# main.net
KiCad netlist of a schematic drawn in EAGLE
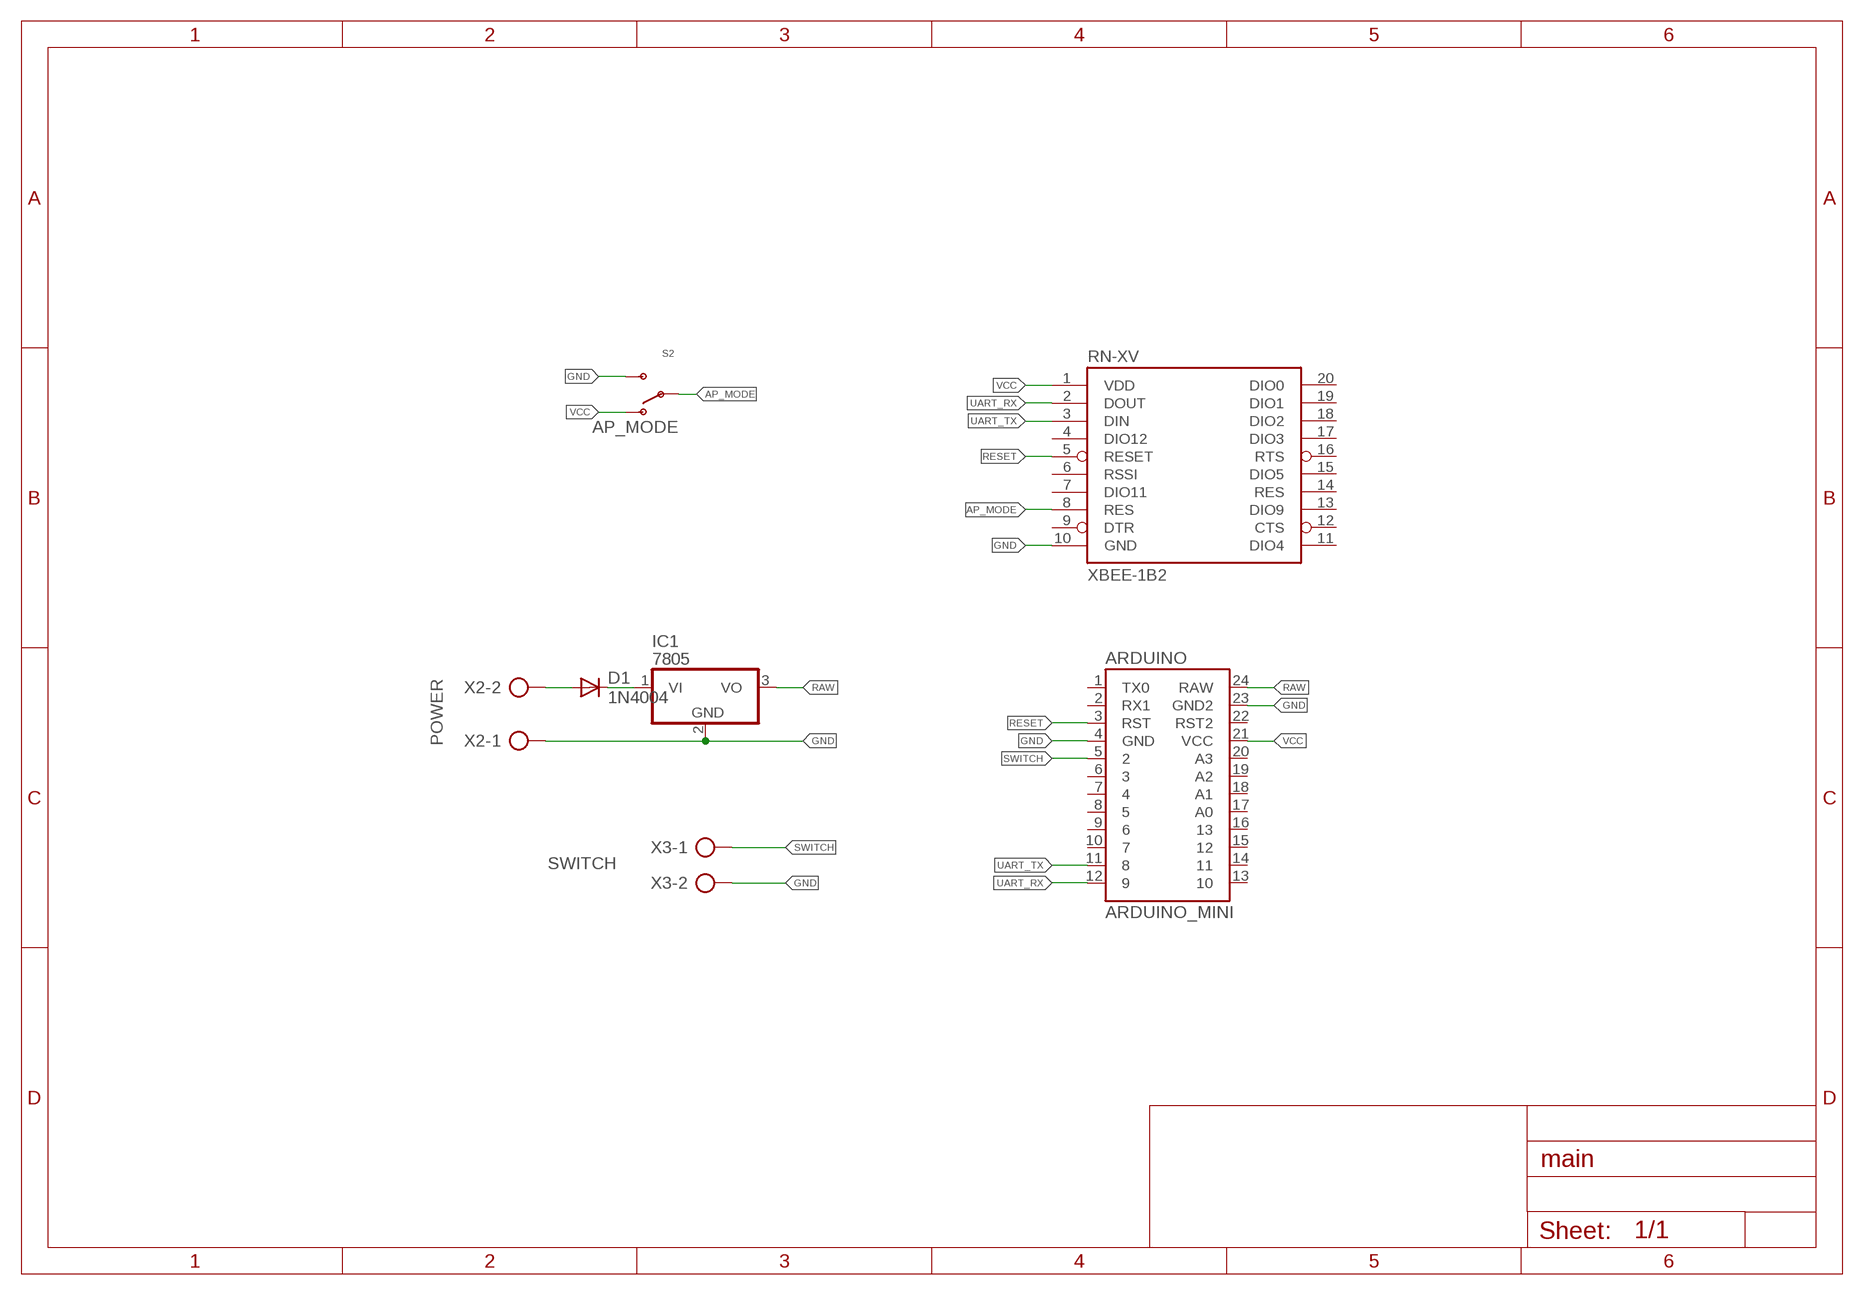
[diagram p0: schematic, sheet 1]

(export (version "E")
  (design (tool "Eeschema 10.0.6"))
  (components
    (comp (ref "ARDUINO")
      (value "ARDUINO_MINI")
      (footprint "eagle-import:ARDUINO_MINI")
      (libsource (lib "eagle-import") (part "ARDUINO_MINI"))
    )
    (comp (ref "D1")
      (value "1N4004")
      (footprint "eagle-import:DO41-10")
      (libsource (lib "eagle-import") (part "1N4004"))
    )
    (comp (ref "IC1")
      (value "7805")
      (footprint "eagle-import:TO220V")
      (libsource (lib "eagle-import") (part "78TV6"))
    )
    (comp (ref "RN-XV")
      (value "XBEE-1B2")
      (footprint "eagle-import:XBEE-SILK")
      (libsource (lib "eagle-import") (part "XBEE-1B2"))
    )
    (comp (ref "S2")
      (value "AP_MODE")
      (footprint "eagle-import:SWITCH-SPDT")
      (libsource (lib "eagle-import") (part "SWITCH-SPDTPTH"))
    )
    (comp (ref "X2")
      (value "POWER")
      (footprint "eagle-import:AK500_2")
      (libsource (lib "eagle-import") (part "AK500/2"))
    )
    (comp (ref "X3")
      (value "SWITCH")
      (footprint "eagle-import:AK500_2")
      (fields (field (name "OC_FARNELL") "unknown") (field (name "OC_NEWARK") "unknown"))
      (libsource (lib "eagle-import") (part "AK500/2"))
    )
  )
  (nets
    (net (code "1") (name "AP_MODE") (class "Default")
      (node (ref "RN-XV") (pin "8") (pinfunction "RES_8") (pintype "bidirectional"))
      (node (ref "S2") (pin "2") (pinfunction "P_2") (pintype "passive"))
    )
    (net (code "2") (name "GND") (class "Default")
      (node (ref "ARDUINO") (pin "23") (pinfunction "GND2_23") (pintype "bidirectional"))
      (node (ref "ARDUINO") (pin "4") (pinfunction "GND_4") (pintype "bidirectional"))
      (node (ref "IC1") (pin "2") (pinfunction "GND_2") (pintype "passive"))
      (node (ref "RN-XV") (pin "10") (pinfunction "GND_10") (pintype "power_in"))
      (node (ref "S2") (pin "3") (pinfunction "S_3") (pintype "passive"))
      (node (ref "X2") (pin "1") (pinfunction "KL_1") (pintype "passive"))
      (node (ref "X3") (pin "2") (pinfunction "KL_2") (pintype "passive"))
    )
    (net (code "3") (name "Net-(IC1-VI)") (class "Default")
      (node (ref "D1") (pin "C") (pinfunction "C_C") (pintype "passive"))
      (node (ref "IC1") (pin "1") (pinfunction "VI_1") (pintype "input"))
    )
    (net (code "4") (name "Net-(X2B-KL)") (class "Default")
      (node (ref "D1") (pin "A") (pinfunction "A_A") (pintype "passive"))
      (node (ref "X2") (pin "2") (pinfunction "KL_2") (pintype "passive"))
    )
    (net (code "5") (name "RAW") (class "Default")
      (node (ref "ARDUINO") (pin "24") (pinfunction "RAW_24") (pintype "bidirectional"))
      (node (ref "IC1") (pin "3") (pinfunction "VO_3") (pintype "passive"))
    )
    (net (code "6") (name "RESET") (class "Default")
      (node (ref "ARDUINO") (pin "3") (pinfunction "RST_3") (pintype "bidirectional"))
      (node (ref "RN-XV") (pin "5") (pinfunction "RESET_5") (pintype "input"))
    )
    (net (code "7") (name "SWITCH") (class "Default")
      (node (ref "ARDUINO") (pin "5") (pinfunction "2_5") (pintype "bidirectional"))
      (node (ref "X3") (pin "1") (pinfunction "KL_1") (pintype "passive"))
    )
    (net (code "8") (name "UART_RX") (class "Default")
      (node (ref "ARDUINO") (pin "12") (pinfunction "9_12") (pintype "bidirectional"))
      (node (ref "RN-XV") (pin "2") (pinfunction "DOUT_2") (pintype "output"))
    )
    (net (code "9") (name "UART_TX") (class "Default")
      (node (ref "ARDUINO") (pin "11") (pinfunction "8_11") (pintype "bidirectional"))
      (node (ref "RN-XV") (pin "3") (pinfunction "DIN_3") (pintype "input"))
    )
    (net (code "10") (name "VCC") (class "Default")
      (node (ref "ARDUINO") (pin "21") (pinfunction "VCC_21") (pintype "bidirectional"))
      (node (ref "RN-XV") (pin "1") (pinfunction "VDD_1") (pintype "power_in"))
      (node (ref "S2") (pin "1") (pinfunction "O_1") (pintype "passive"))
    )
    (net (code "11") (name "unconnected-(ARDUINO-3-Pad6)") (class "Default")
      (node (ref "ARDUINO") (pin "6") (pinfunction "3_6") (pintype "bidirectional"))
    )
    (net (code "12") (name "unconnected-(ARDUINO-4-Pad7)") (class "Default")
      (node (ref "ARDUINO") (pin "7") (pinfunction "4_7") (pintype "bidirectional"))
    )
    (net (code "13") (name "unconnected-(ARDUINO-5-Pad8)") (class "Default")
      (node (ref "ARDUINO") (pin "8") (pinfunction "5_8") (pintype "bidirectional"))
    )
    (net (code "14") (name "unconnected-(ARDUINO-6-Pad9)") (class "Default")
      (node (ref "ARDUINO") (pin "9") (pinfunction "6_9") (pintype "bidirectional"))
    )
    (net (code "15") (name "unconnected-(ARDUINO-7-Pad10)") (class "Default")
      (node (ref "ARDUINO") (pin "10") (pinfunction "7_10") (pintype "bidirectional"))
    )
    (net (code "16") (name "unconnected-(ARDUINO-10-Pad13)") (class "Default")
      (node (ref "ARDUINO") (pin "13") (pinfunction "10_13") (pintype "bidirectional"))
    )
    (net (code "17") (name "unconnected-(ARDUINO-11-Pad14)") (class "Default")
      (node (ref "ARDUINO") (pin "14") (pinfunction "11_14") (pintype "bidirectional"))
    )
    (net (code "18") (name "unconnected-(ARDUINO-12-Pad15)") (class "Default")
      (node (ref "ARDUINO") (pin "15") (pinfunction "12_15") (pintype "bidirectional"))
    )
    (net (code "19") (name "unconnected-(ARDUINO-13-Pad16)") (class "Default")
      (node (ref "ARDUINO") (pin "16") (pinfunction "13_16") (pintype "bidirectional"))
    )
    (net (code "20") (name "unconnected-(ARDUINO-A0-Pad17)") (class "Default")
      (node (ref "ARDUINO") (pin "17") (pinfunction "A0_17") (pintype "bidirectional"))
    )
    (net (code "21") (name "unconnected-(ARDUINO-A1-Pad18)") (class "Default")
      (node (ref "ARDUINO") (pin "18") (pinfunction "A1_18") (pintype "bidirectional"))
    )
    (net (code "22") (name "unconnected-(ARDUINO-A2-Pad19)") (class "Default")
      (node (ref "ARDUINO") (pin "19") (pinfunction "A2_19") (pintype "bidirectional"))
    )
    (net (code "23") (name "unconnected-(ARDUINO-A3-Pad20)") (class "Default")
      (node (ref "ARDUINO") (pin "20") (pinfunction "A3_20") (pintype "bidirectional"))
    )
    (net (code "24") (name "unconnected-(ARDUINO-RST2-Pad22)") (class "Default")
      (node (ref "ARDUINO") (pin "22") (pinfunction "RST2_22") (pintype "bidirectional"))
    )
    (net (code "25") (name "unconnected-(ARDUINO-RX1-Pad2)") (class "Default")
      (node (ref "ARDUINO") (pin "2") (pinfunction "RX1_2") (pintype "bidirectional"))
    )
    (net (code "26") (name "unconnected-(ARDUINO-TX0-Pad1)") (class "Default")
      (node (ref "ARDUINO") (pin "1") (pinfunction "TX0_1") (pintype "bidirectional"))
    )
    (net (code "27") (name "unconnected-(RN-XV-CTS-Pad12)") (class "Default")
      (node (ref "RN-XV") (pin "12") (pinfunction "CTS_12") (pintype "output"))
    )
    (net (code "28") (name "unconnected-(RN-XV-DIO0-Pad20)") (class "Default")
      (node (ref "RN-XV") (pin "20") (pinfunction "DIO0_20") (pintype "bidirectional"))
    )
    (net (code "29") (name "unconnected-(RN-XV-DIO1-Pad19)") (class "Default")
      (node (ref "RN-XV") (pin "19") (pinfunction "DIO1_19") (pintype "bidirectional"))
    )
    (net (code "30") (name "unconnected-(RN-XV-DIO2-Pad18)") (class "Default")
      (node (ref "RN-XV") (pin "18") (pinfunction "DIO2_18") (pintype "bidirectional"))
    )
    (net (code "31") (name "unconnected-(RN-XV-DIO3-Pad17)") (class "Default")
      (node (ref "RN-XV") (pin "17") (pinfunction "DIO3_17") (pintype "bidirectional"))
    )
    (net (code "32") (name "unconnected-(RN-XV-DIO4-Pad11)") (class "Default")
      (node (ref "RN-XV") (pin "11") (pinfunction "DIO4_11") (pintype "bidirectional"))
    )
    (net (code "33") (name "unconnected-(RN-XV-DIO5-Pad15)") (class "Default")
      (node (ref "RN-XV") (pin "15") (pinfunction "DIO5_15") (pintype "bidirectional"))
    )
    (net (code "34") (name "unconnected-(RN-XV-DIO9-Pad13)") (class "Default")
      (node (ref "RN-XV") (pin "13") (pinfunction "DIO9_13") (pintype "bidirectional"))
    )
    (net (code "35") (name "unconnected-(RN-XV-DIO11-Pad7)") (class "Default")
      (node (ref "RN-XV") (pin "7") (pinfunction "DIO11_7") (pintype "bidirectional"))
    )
    (net (code "36") (name "unconnected-(RN-XV-DIO12-Pad4)") (class "Default")
      (node (ref "RN-XV") (pin "4") (pinfunction "DIO12_4") (pintype "bidirectional"))
    )
    (net (code "37") (name "unconnected-(RN-XV-DTR-Pad9)") (class "Default")
      (node (ref "RN-XV") (pin "9") (pinfunction "DTR_9") (pintype "bidirectional"))
    )
    (net (code "38") (name "unconnected-(RN-XV-RES-Pad14)") (class "Default")
      (node (ref "RN-XV") (pin "14") (pinfunction "RES_14") (pintype "bidirectional"))
    )
    (net (code "39") (name "unconnected-(RN-XV-RSSI-Pad6)") (class "Default")
      (node (ref "RN-XV") (pin "6") (pinfunction "RSSI_6") (pintype "bidirectional"))
    )
    (net (code "40") (name "unconnected-(RN-XV-RTS-Pad16)") (class "Default")
      (node (ref "RN-XV") (pin "16") (pinfunction "RTS_16") (pintype "input"))
    )
  )
)
